# fpga-bank7.net
KiCad netlist of a schematic drawn in Altium Designer
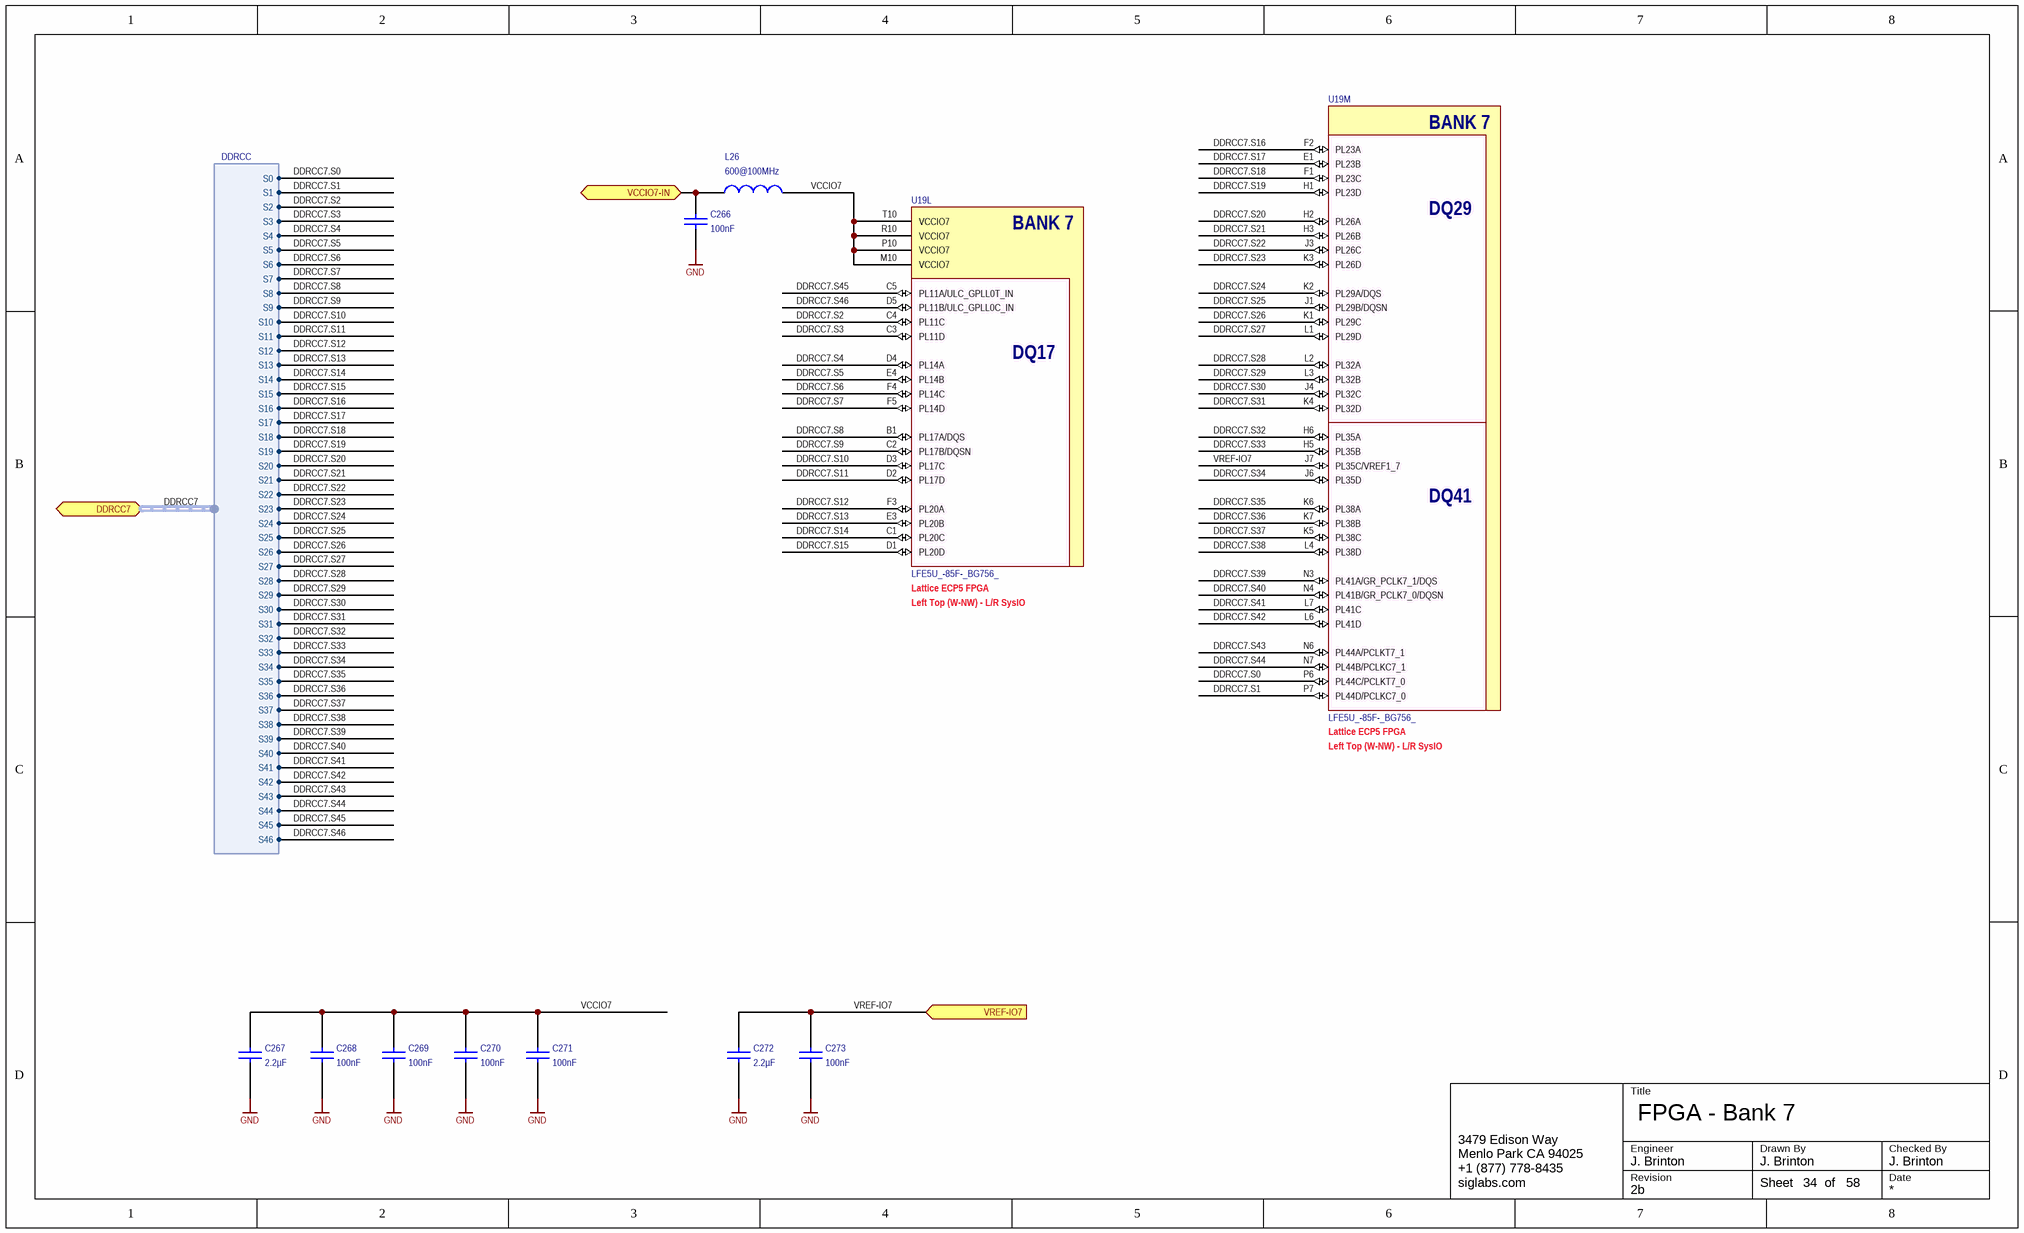
[diagram p0: fpga-bank7.SchDoc]

(export (version "E")
  (design (tool "Eeschema 10.0.6"))
  (components
    (comp (ref "C266")
      (value "100nF")
      (footprint "generic:CAPC1005X56N")
      (description "Ceramic Capacitor 100nF ±10% 16V X7R 0402")
      (fields (field (name "MANUFACTURER") "Murata") (field (name "TOLERANCE") "±10%"))
      (libsource (lib "murata") (part "GRM155R71A104KA01J"))
    )
    (comp (ref "C267")
      (value "2.2µF")
      (footprint "generic:CAPC1608X90N")
      (description "Ceramic Capacitor 2.2uF ±10% 10V X7R 0603")
      (fields (field (name "MANUFACTURER") "Murata") (field (name "TOLERANCE") "±10%"))
      (libsource (lib "murata") (part "GRM188R71A225KE15D"))
    )
    (comp (ref "C268")
      (value "100nF")
      (footprint "generic:CAPC1005X56N")
      (description "Ceramic Capacitor 100nF ±10% 16V X7R 0402")
      (fields (field (name "MANUFACTURER") "Murata") (field (name "TOLERANCE") "±10%"))
      (libsource (lib "murata") (part "GRM155R71A104KA01J"))
    )
    (comp (ref "C269")
      (value "100nF")
      (footprint "generic:CAPC1005X56N")
      (description "Ceramic Capacitor 100nF ±10% 16V X7R 0402")
      (fields (field (name "MANUFACTURER") "Murata") (field (name "TOLERANCE") "±10%"))
      (libsource (lib "murata") (part "GRM155R71A104KA01J"))
    )
    (comp (ref "C270")
      (value "100nF")
      (footprint "generic:CAPC1005X56N")
      (description "Ceramic Capacitor 100nF ±10% 16V X7R 0402")
      (fields (field (name "MANUFACTURER") "Murata") (field (name "TOLERANCE") "±10%"))
      (libsource (lib "murata") (part "GRM155R71A104KA01J"))
    )
    (comp (ref "C271")
      (value "100nF")
      (footprint "generic:CAPC1005X56N")
      (description "Ceramic Capacitor 100nF ±10% 16V X7R 0402")
      (fields (field (name "MANUFACTURER") "Murata") (field (name "TOLERANCE") "±10%"))
      (libsource (lib "murata") (part "GRM155R71A104KA01J"))
    )
    (comp (ref "C272")
      (value "2.2µF")
      (footprint "generic:CAPC1608X90N")
      (description "Ceramic Capacitor 2.2uF ±10% 10V X7R 0603")
      (fields (field (name "MANUFACTURER") "Murata") (field (name "TOLERANCE") "±10%"))
      (libsource (lib "murata") (part "GRM188R71A225KE15D"))
    )
    (comp (ref "C273")
      (value "100nF")
      (footprint "generic:CAPC1005X56N")
      (description "Ceramic Capacitor 100nF ±10% 16V X7R 0402")
      (fields (field (name "MANUFACTURER") "Murata") (field (name "TOLERANCE") "±10%"))
      (libsource (lib "murata") (part "GRM155R71A104KA01J"))
    )
    (comp (ref "L26")
      (value "600@100MHz")
      (footprint "0402")
      (description "Ferrite Bead 600-Ohm @ 100MHz 900mA 0402")
      (fields (field (name "MANUFACTURER") "Murata") (field (name "TOLERANCE") "±25%"))
      (libsource (lib "Graviton") (part "IND 0402"))
    )
    (comp (ref "U19")
      (value "LFE5U_-85F-_BG756_")
      (footprint "lattice:caBGA756")
      (description "ECP5 FPGA, 85k LUT, 756-caBGA")
      (fields (field (name "MANUFACTURER") "Lattice Semiconductor"))
      (libsource (lib "lattice") (part "LFE5U_-85F-_BG756_"))
    )
  )
  (nets
    (net (code "2") (name "/DDRCC7.S0") (class "Default")
      (node (ref "U19") (pin "P6") (pinfunction "PL44C/PCLKT7_0_P6") (pintype "bidirectional"))
    )
    (net (code "3") (name "/DDRCC7.S1") (class "Default")
      (node (ref "U19") (pin "P7") (pinfunction "PL44D/PCLKC7_0_P7") (pintype "bidirectional"))
    )
    (net (code "4") (name "/DDRCC7.S2") (class "Default")
      (node (ref "U19") (pin "C4") (pinfunction "PL11C_C4") (pintype "bidirectional"))
    )
    (net (code "5") (name "/DDRCC7.S3") (class "Default")
      (node (ref "U19") (pin "C3") (pinfunction "PL11D_C3") (pintype "bidirectional"))
    )
    (net (code "6") (name "/DDRCC7.S4") (class "Default")
      (node (ref "U19") (pin "D4") (pinfunction "PL14A_D4") (pintype "bidirectional"))
    )
    (net (code "7") (name "/DDRCC7.S5") (class "Default")
      (node (ref "U19") (pin "E4") (pinfunction "PL14B_E4") (pintype "bidirectional"))
    )
    (net (code "8") (name "/DDRCC7.S6") (class "Default")
      (node (ref "U19") (pin "F4") (pinfunction "PL14C_F4") (pintype "bidirectional"))
    )
    (net (code "9") (name "/DDRCC7.S7") (class "Default")
      (node (ref "U19") (pin "F5") (pinfunction "PL14D_F5") (pintype "bidirectional"))
    )
    (net (code "10") (name "/DDRCC7.S8") (class "Default")
      (node (ref "U19") (pin "B1") (pinfunction "PL17A/DQS_B1") (pintype "bidirectional"))
    )
    (net (code "11") (name "/DDRCC7.S9") (class "Default")
      (node (ref "U19") (pin "C2") (pinfunction "PL17B/DQSN_C2") (pintype "bidirectional"))
    )
    (net (code "12") (name "/DDRCC7.S10") (class "Default")
      (node (ref "U19") (pin "D3") (pinfunction "PL17C_D3") (pintype "bidirectional"))
    )
    (net (code "13") (name "/DDRCC7.S11") (class "Default")
      (node (ref "U19") (pin "D2") (pinfunction "PL17D_D2") (pintype "bidirectional"))
    )
    (net (code "14") (name "/DDRCC7.S12") (class "Default")
      (node (ref "U19") (pin "F3") (pinfunction "PL20A_F3") (pintype "bidirectional"))
    )
    (net (code "15") (name "/DDRCC7.S13") (class "Default")
      (node (ref "U19") (pin "E3") (pinfunction "PL20B_E3") (pintype "bidirectional"))
    )
    (net (code "16") (name "/DDRCC7.S14") (class "Default")
      (node (ref "U19") (pin "C1") (pinfunction "PL20C_C1") (pintype "bidirectional"))
    )
    (net (code "17") (name "/DDRCC7.S15") (class "Default")
      (node (ref "U19") (pin "D1") (pinfunction "PL20D_D1") (pintype "bidirectional"))
    )
    (net (code "18") (name "/DDRCC7.S16") (class "Default")
      (node (ref "U19") (pin "F2") (pinfunction "PL23A_F2") (pintype "bidirectional"))
    )
    (net (code "19") (name "/DDRCC7.S17") (class "Default")
      (node (ref "U19") (pin "E1") (pinfunction "PL23B_E1") (pintype "bidirectional"))
    )
    (net (code "20") (name "/DDRCC7.S18") (class "Default")
      (node (ref "U19") (pin "F1") (pinfunction "PL23C_F1") (pintype "bidirectional"))
    )
    (net (code "21") (name "/DDRCC7.S19") (class "Default")
      (node (ref "U19") (pin "H1") (pinfunction "PL23D_H1") (pintype "bidirectional"))
    )
    (net (code "22") (name "/DDRCC7.S20") (class "Default")
      (node (ref "U19") (pin "H2") (pinfunction "PL26A_H2") (pintype "bidirectional"))
    )
    (net (code "23") (name "/DDRCC7.S21") (class "Default")
      (node (ref "U19") (pin "H3") (pinfunction "PL26B_H3") (pintype "bidirectional"))
    )
    (net (code "24") (name "/DDRCC7.S22") (class "Default")
      (node (ref "U19") (pin "J3") (pinfunction "PL26C_J3") (pintype "bidirectional"))
    )
    (net (code "25") (name "/DDRCC7.S23") (class "Default")
      (node (ref "U19") (pin "K3") (pinfunction "PL26D_K3") (pintype "bidirectional"))
    )
    (net (code "26") (name "/DDRCC7.S24") (class "Default")
      (node (ref "U19") (pin "K2") (pinfunction "PL29A/DQS_K2") (pintype "bidirectional"))
    )
    (net (code "27") (name "/DDRCC7.S25") (class "Default")
      (node (ref "U19") (pin "J1") (pinfunction "PL29B/DQSN_J1") (pintype "bidirectional"))
    )
    (net (code "28") (name "/DDRCC7.S26") (class "Default")
      (node (ref "U19") (pin "K1") (pinfunction "PL29C_K1") (pintype "bidirectional"))
    )
    (net (code "29") (name "/DDRCC7.S27") (class "Default")
      (node (ref "U19") (pin "L1") (pinfunction "PL29D_L1") (pintype "bidirectional"))
    )
    (net (code "30") (name "/DDRCC7.S28") (class "Default")
      (node (ref "U19") (pin "L2") (pinfunction "PL32A_L2") (pintype "bidirectional"))
    )
    (net (code "31") (name "/DDRCC7.S29") (class "Default")
      (node (ref "U19") (pin "L3") (pinfunction "PL32B_L3") (pintype "bidirectional"))
    )
    (net (code "32") (name "/DDRCC7.S30") (class "Default")
      (node (ref "U19") (pin "J4") (pinfunction "PL32C_J4") (pintype "bidirectional"))
    )
    (net (code "33") (name "/DDRCC7.S31") (class "Default")
      (node (ref "U19") (pin "K4") (pinfunction "PL32D_K4") (pintype "bidirectional"))
    )
    (net (code "34") (name "/DDRCC7.S32") (class "Default")
      (node (ref "U19") (pin "H6") (pinfunction "PL35A_H6") (pintype "bidirectional"))
    )
    (net (code "35") (name "/DDRCC7.S33") (class "Default")
      (node (ref "U19") (pin "H5") (pinfunction "PL35B_H5") (pintype "bidirectional"))
    )
    (net (code "36") (name "/DDRCC7.S34") (class "Default")
      (node (ref "U19") (pin "J6") (pinfunction "PL35D_J6") (pintype "bidirectional"))
    )
    (net (code "37") (name "/DDRCC7.S35") (class "Default")
      (node (ref "U19") (pin "K6") (pinfunction "PL38A_K6") (pintype "bidirectional"))
    )
    (net (code "38") (name "/DDRCC7.S36") (class "Default")
      (node (ref "U19") (pin "K7") (pinfunction "PL38B_K7") (pintype "bidirectional"))
    )
    (net (code "39") (name "/DDRCC7.S37") (class "Default")
      (node (ref "U19") (pin "K5") (pinfunction "PL38C_K5") (pintype "bidirectional"))
    )
    (net (code "40") (name "/DDRCC7.S38") (class "Default")
      (node (ref "U19") (pin "L4") (pinfunction "PL38D_L4") (pintype "bidirectional"))
    )
    (net (code "41") (name "/DDRCC7.S39") (class "Default")
      (node (ref "U19") (pin "N3") (pinfunction "PL41A/GR_PCLK7_1/DQS_N3") (pintype "bidirectional"))
    )
    (net (code "42") (name "/DDRCC7.S40") (class "Default")
      (node (ref "U19") (pin "N4") (pinfunction "PL41B/GR_PCLK7_0/DQSN_N4") (pintype "bidirectional"))
    )
    (net (code "43") (name "/DDRCC7.S41") (class "Default")
      (node (ref "U19") (pin "L7") (pinfunction "PL41C_L7") (pintype "bidirectional"))
    )
    (net (code "44") (name "/DDRCC7.S42") (class "Default")
      (node (ref "U19") (pin "L6") (pinfunction "PL41D_L6") (pintype "bidirectional"))
    )
    (net (code "45") (name "/DDRCC7.S43") (class "Default")
      (node (ref "U19") (pin "N6") (pinfunction "PL44A/PCLKT7_1_N6") (pintype "bidirectional"))
    )
    (net (code "46") (name "/DDRCC7.S44") (class "Default")
      (node (ref "U19") (pin "N7") (pinfunction "PL44B/PCLKC7_1_N7") (pintype "bidirectional"))
    )
    (net (code "47") (name "/DDRCC7.S45") (class "Default")
      (node (ref "U19") (pin "C5") (pinfunction "PL11A/ULC_GPLL0T_IN_C5") (pintype "bidirectional"))
    )
    (net (code "48") (name "/DDRCC7.S46") (class "Default")
      (node (ref "U19") (pin "D5") (pinfunction "PL11B/ULC_GPLL0C_IN_D5") (pintype "bidirectional"))
    )
    (net (code "50") (name "/VCCIO7") (class "Default")
      (node (ref "C267") (pin "2") (pinfunction "2_2") (pintype "passive"))
      (node (ref "C268") (pin "2") (pinfunction "2_2") (pintype "passive"))
      (node (ref "C269") (pin "2") (pinfunction "2_2") (pintype "passive"))
      (node (ref "C270") (pin "2") (pinfunction "2_2") (pintype "passive"))
      (node (ref "C271") (pin "2") (pinfunction "2_2") (pintype "passive"))
      (node (ref "L26") (pin "1") (pinfunction "1_1") (pintype "passive"))
      (node (ref "U19") (pin "M10") (pinfunction "VCCIO7_M10") (pintype "power_in"))
      (node (ref "U19") (pin "P10") (pinfunction "VCCIO7_P10") (pintype "power_in"))
      (node (ref "U19") (pin "R10") (pinfunction "VCCIO7_R10") (pintype "power_in"))
      (node (ref "U19") (pin "T10") (pinfunction "VCCIO7_T10") (pintype "power_in"))
    )
    (net (code "51") (name "/VCCIO7-IN") (class "Default")
      (node (ref "C266") (pin "2") (pinfunction "2_2") (pintype "passive"))
      (node (ref "L26") (pin "2") (pinfunction "2_2") (pintype "passive"))
    )
    (net (code "52") (name "/VREF-IO7") (class "Default")
      (node (ref "C272") (pin "2") (pinfunction "2_2") (pintype "passive"))
      (node (ref "C273") (pin "2") (pinfunction "2_2") (pintype "passive"))
      (node (ref "U19") (pin "J7") (pinfunction "PL35C/VREF1_7_J7") (pintype "bidirectional"))
    )
    (net (code "53") (name "GND") (class "Default")
      (node (ref "C266") (pin "1") (pinfunction "1_1") (pintype "passive"))
      (node (ref "C267") (pin "1") (pinfunction "1_1") (pintype "passive"))
      (node (ref "C268") (pin "1") (pinfunction "1_1") (pintype "passive"))
      (node (ref "C269") (pin "1") (pinfunction "1_1") (pintype "passive"))
      (node (ref "C270") (pin "1") (pinfunction "1_1") (pintype "passive"))
      (node (ref "C271") (pin "1") (pinfunction "1_1") (pintype "passive"))
      (node (ref "C272") (pin "1") (pinfunction "1_1") (pintype "passive"))
      (node (ref "C273") (pin "1") (pinfunction "1_1") (pintype "passive"))
    )
  )
)
